# FilterBoard_Schematic.net
KiCad netlist of a schematic drawn in Altium Designer
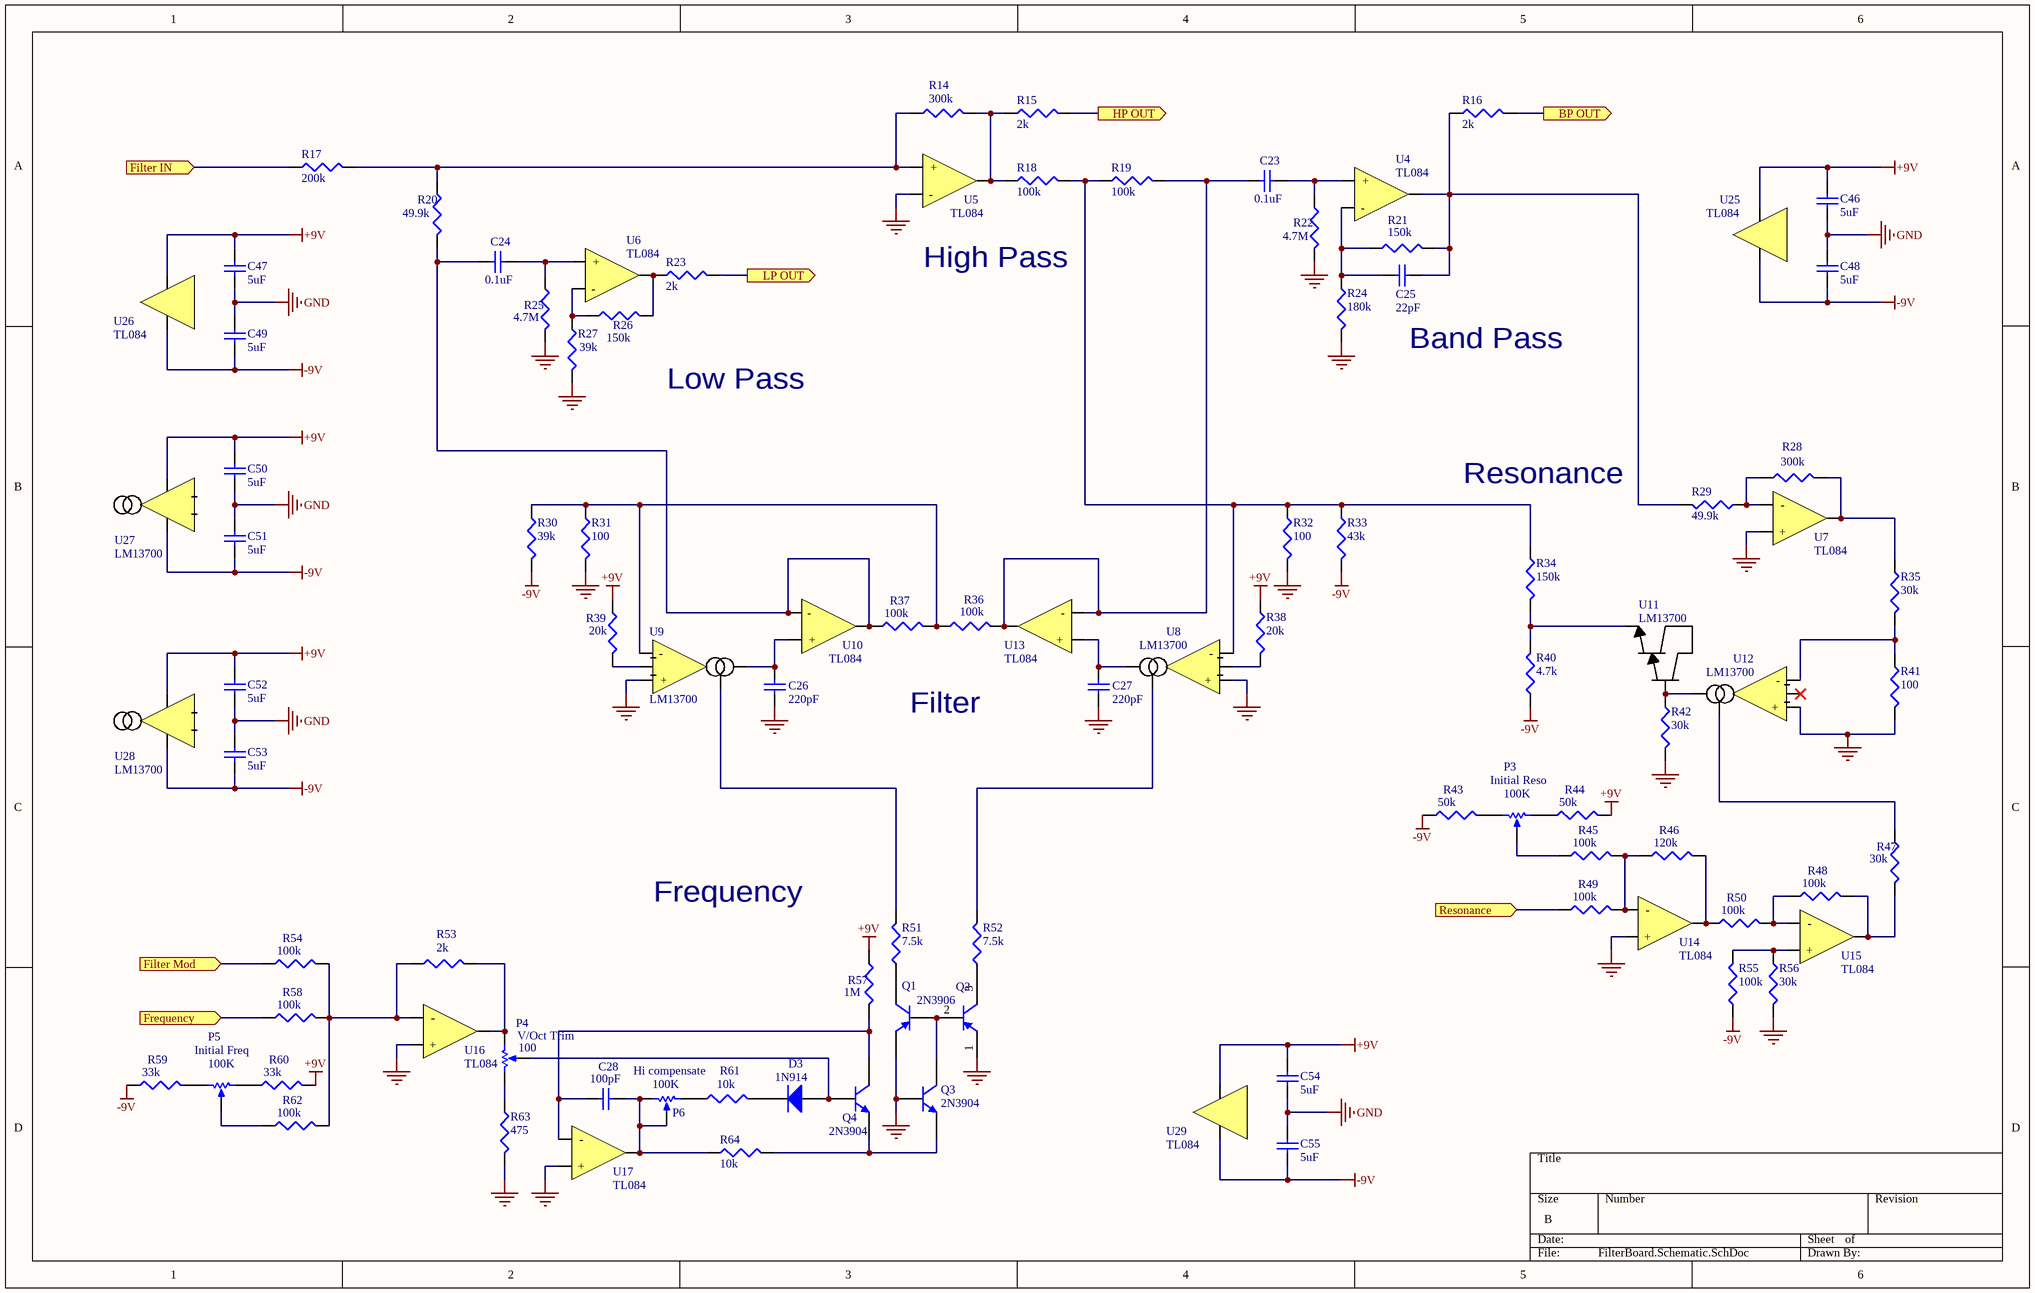
[diagram p0: FilterBoard.Schematic.SchDoc]

(export (version "E")
  (design (tool "Eeschema 10.0.6"))
  (components
    (comp (ref "C23")
      (value "0.1uF")
      (footprint "CAPC1608N")
      (description "Capacitor (Semiconductor SIM Model)")
      (fields (field (name "PUBLISHER") "Altium Limited"))
      (libsource (lib "Miscellaneous Devices") (part "Cap Semi"))
    )
    (comp (ref "C24")
      (value "0.1uF")
      (footprint "CAPC1608N")
      (description "Capacitor (Semiconductor SIM Model)")
      (fields (field (name "PUBLISHER") "Altium Limited"))
      (libsource (lib "Miscellaneous Devices") (part "Cap Semi"))
    )
    (comp (ref "C25")
      (value "22pF")
      (footprint "CAPC1608N")
      (description "Capacitor (Semiconductor SIM Model)")
      (fields (field (name "PUBLISHER") "Altium Limited"))
      (libsource (lib "Miscellaneous Devices") (part "Cap Semi"))
    )
    (comp (ref "C26")
      (value "220pF")
      (footprint "CAPC1608N")
      (description "Capacitor (Semiconductor SIM Model)")
      (fields (field (name "PUBLISHER") "Altium Limited"))
      (libsource (lib "Miscellaneous Devices") (part "Cap Semi"))
    )
    (comp (ref "C27")
      (value "220pF")
      (footprint "CAPC1608N")
      (description "Capacitor (Semiconductor SIM Model)")
      (fields (field (name "PUBLISHER") "Altium Limited"))
      (libsource (lib "Miscellaneous Devices") (part "Cap Semi"))
    )
    (comp (ref "C28")
      (value "100pF")
      (footprint "CAPC1608N")
      (description "Capacitor (Semiconductor SIM Model)")
      (fields (field (name "PUBLISHER") "Altium Limited"))
      (libsource (lib "Miscellaneous Devices") (part "Cap Semi"))
    )
    (comp (ref "C46")
      (value "5uF")
      (footprint "CAPC1608N")
      (description "Capacitor (Semiconductor SIM Model)")
      (fields (field (name "PUBLISHER") "Altium Limited"))
      (libsource (lib "Miscellaneous Devices") (part "Cap Semi"))
    )
    (comp (ref "C47")
      (value "5uF")
      (footprint "CAPC1608N")
      (description "Capacitor (Semiconductor SIM Model)")
      (fields (field (name "PUBLISHER") "Altium Limited"))
      (libsource (lib "Miscellaneous Devices") (part "Cap Semi"))
    )
    (comp (ref "C48")
      (value "5uF")
      (footprint "CAPC1608N")
      (description "Capacitor (Semiconductor SIM Model)")
      (fields (field (name "PUBLISHER") "Altium Limited"))
      (libsource (lib "Miscellaneous Devices") (part "Cap Semi"))
    )
    (comp (ref "C49")
      (value "5uF")
      (footprint "CAPC1608N")
      (description "Capacitor (Semiconductor SIM Model)")
      (fields (field (name "PUBLISHER") "Altium Limited"))
      (libsource (lib "Miscellaneous Devices") (part "Cap Semi"))
    )
    (comp (ref "C50")
      (value "5uF")
      (footprint "CAPC1608N")
      (description "Capacitor (Semiconductor SIM Model)")
      (fields (field (name "PUBLISHER") "Altium Limited"))
      (libsource (lib "Miscellaneous Devices") (part "Cap Semi"))
    )
    (comp (ref "C51")
      (value "5uF")
      (footprint "CAPC1608N")
      (description "Capacitor (Semiconductor SIM Model)")
      (fields (field (name "PUBLISHER") "Altium Limited"))
      (libsource (lib "Miscellaneous Devices") (part "Cap Semi"))
    )
    (comp (ref "C52")
      (value "5uF")
      (footprint "CAPC1608N")
      (description "Capacitor (Semiconductor SIM Model)")
      (fields (field (name "PUBLISHER") "Altium Limited"))
      (libsource (lib "Miscellaneous Devices") (part "Cap Semi"))
    )
    (comp (ref "C53")
      (value "5uF")
      (footprint "CAPC1608N")
      (description "Capacitor (Semiconductor SIM Model)")
      (fields (field (name "PUBLISHER") "Altium Limited"))
      (libsource (lib "Miscellaneous Devices") (part "Cap Semi"))
    )
    (comp (ref "C54")
      (value "5uF")
      (footprint "CAPC1608N")
      (description "Capacitor (Semiconductor SIM Model)")
      (fields (field (name "PUBLISHER") "Altium Limited"))
      (libsource (lib "Miscellaneous Devices") (part "Cap Semi"))
    )
    (comp (ref "C55")
      (value "5uF")
      (footprint "CAPC1608N")
      (description "Capacitor (Semiconductor SIM Model)")
      (fields (field (name "PUBLISHER") "Altium Limited"))
      (libsource (lib "Miscellaneous Devices") (part "Cap Semi"))
    )
    (comp (ref "D3")
      (value "1N914")
      (footprint "1N914")
      (description "1 Amp General Purpose Rectifier")
      (fields (field (name "PUBLISHER") "Altium Limited"))
      (libsource (lib "Miscellaneous Devices") (part "Diode 1N4001"))
    )
    (comp (ref "P3")
      (value "Initial Reso")
      (footprint "BOURNS Trim pot")
      (description "Potentiometer")
      (fields (field (name "ALTIUM_VALUE") "100K") (field (name "PUBLISHER") "Altium Limited"))
      (libsource (lib "Miscellaneous Devices") (part "RPot"))
    )
    (comp (ref "P4")
      (value "V/Oct Trim")
      (footprint "BOURNS Trim pot")
      (description "Potentiometer")
      (fields (field (name "ALTIUM_VALUE") "100") (field (name "PUBLISHER") "Altium Limited"))
      (libsource (lib "Miscellaneous Devices") (part "RPot"))
    )
    (comp (ref "P5")
      (value "Initial Freq")
      (footprint "BOURNS Trim pot")
      (description "Potentiometer")
      (fields (field (name "ALTIUM_VALUE") "100K") (field (name "PUBLISHER") "Altium Limited"))
      (libsource (lib "Miscellaneous Devices") (part "RPot"))
    )
    (comp (ref "P6")
      (value "Hi compensate")
      (footprint "BOURNS Trim pot")
      (description "Potentiometer")
      (fields (field (name "ALTIUM_VALUE") "100K") (field (name "PUBLISHER") "Altium Limited"))
      (libsource (lib "Miscellaneous Devices") (part "RPot"))
    )
    (comp (ref "Q1")
      (value "2N3906")
      (footprint "2N3906")
      (description "PNP General Purpose Amplifier")
      (fields (field (name "PUBLISHER") "Altium Limited"))
      (libsource (lib "") (part "2N3906_1"))
    )
    (comp (ref "Q2")
      (value "2N3906")
      (footprint "2N3906")
      (description "PNP General Purpose Amplifier")
      (fields (field (name "PUBLISHER") "Altium Limited"))
      (libsource (lib "Miscellaneous Devices") (part "2N3906"))
    )
    (comp (ref "Q3")
      (value "2N3904")
      (footprint "2N3906")
      (description "NPN General Purpose Amplifier")
      (fields (field (name "PUBLISHER") "Altium Limited"))
      (libsource (lib "Miscellaneous Devices") (part "2N3904"))
    )
    (comp (ref "Q4")
      (value "2N3904")
      (footprint "2N3906")
      (description "NPN General Purpose Amplifier")
      (fields (field (name "PUBLISHER") "Altium Limited"))
      (libsource (lib "Miscellaneous Devices") (part "2N3904"))
    )
    (comp (ref "R14")
      (value "300k")
      (footprint "CAPC1608N")
      (description "Resistor")
      (fields (field (name "PUBLISHER") "Altium Limited"))
      (libsource (lib "Miscellaneous Devices") (part "Res3"))
    )
    (comp (ref "R15")
      (value "2k")
      (footprint "CAPC1608N")
      (description "Resistor")
      (fields (field (name "PUBLISHER") "Altium Limited"))
      (libsource (lib "Miscellaneous Devices") (part "Res3"))
    )
    (comp (ref "R16")
      (value "2k")
      (footprint "CAPC1608N")
      (description "Resistor")
      (fields (field (name "PUBLISHER") "Altium Limited"))
      (libsource (lib "Miscellaneous Devices") (part "Res3"))
    )
    (comp (ref "R17")
      (value "200k")
      (footprint "CAPC1608N")
      (description "Resistor")
      (fields (field (name "PUBLISHER") "Altium Limited"))
      (libsource (lib "Miscellaneous Devices") (part "Res3"))
    )
    (comp (ref "R18")
      (value "100k")
      (footprint "CAPC1608N")
      (description "Resistor")
      (fields (field (name "PUBLISHER") "Altium Limited"))
      (libsource (lib "Miscellaneous Devices") (part "Res3"))
    )
    (comp (ref "R19")
      (value "100k")
      (footprint "CAPC1608N")
      (description "Resistor")
      (fields (field (name "PUBLISHER") "Altium Limited"))
      (libsource (lib "Miscellaneous Devices") (part "Res3"))
    )
    (comp (ref "R20")
      (value "49.9k")
      (footprint "CAPC1608N")
      (description "Resistor")
      (fields (field (name "PUBLISHER") "Altium Limited"))
      (libsource (lib "Miscellaneous Devices") (part "Res3"))
    )
    (comp (ref "R21")
      (value "150k")
      (footprint "CAPC1608N")
      (description "Resistor")
      (fields (field (name "PUBLISHER") "Altium Limited"))
      (libsource (lib "Miscellaneous Devices") (part "Res3"))
    )
    (comp (ref "R22")
      (value "4.7M")
      (footprint "CAPC1608N")
      (description "Resistor")
      (fields (field (name "PUBLISHER") "Altium Limited"))
      (libsource (lib "Miscellaneous Devices") (part "Res3"))
    )
    (comp (ref "R23")
      (value "2k")
      (footprint "CAPC1608N")
      (description "Resistor")
      (fields (field (name "PUBLISHER") "Altium Limited"))
      (libsource (lib "Miscellaneous Devices") (part "Res3"))
    )
    (comp (ref "R24")
      (value "180k")
      (footprint "CAPC1608N")
      (description "Resistor")
      (fields (field (name "PUBLISHER") "Altium Limited"))
      (libsource (lib "Miscellaneous Devices") (part "Res3"))
    )
    (comp (ref "R25")
      (value "4.7M")
      (footprint "CAPC1608N")
      (description "Resistor")
      (fields (field (name "PUBLISHER") "Altium Limited"))
      (libsource (lib "Miscellaneous Devices") (part "Res3"))
    )
    (comp (ref "R26")
      (value "150k")
      (footprint "CAPC1608N")
      (description "Resistor")
      (fields (field (name "PUBLISHER") "Altium Limited"))
      (libsource (lib "Miscellaneous Devices") (part "Res3"))
    )
    (comp (ref "R27")
      (value "39k")
      (footprint "CAPC1608N")
      (description "Resistor")
      (fields (field (name "PUBLISHER") "Altium Limited"))
      (libsource (lib "Miscellaneous Devices") (part "Res3"))
    )
    (comp (ref "R28")
      (value "300k")
      (footprint "CAPC1608N")
      (description "Resistor")
      (fields (field (name "PUBLISHER") "Altium Limited"))
      (libsource (lib "Miscellaneous Devices") (part "Res3"))
    )
    (comp (ref "R29")
      (value "49.9k")
      (footprint "CAPC1608N")
      (description "Resistor")
      (fields (field (name "PUBLISHER") "Altium Limited"))
      (libsource (lib "Miscellaneous Devices") (part "Res3"))
    )
    (comp (ref "R30")
      (value "39k")
      (footprint "CAPC1608N")
      (description "Resistor")
      (fields (field (name "PUBLISHER") "Altium Limited"))
      (libsource (lib "Miscellaneous Devices") (part "Res3"))
    )
    (comp (ref "R31")
      (value "100")
      (footprint "CAPC1608N")
      (description "Resistor")
      (fields (field (name "PUBLISHER") "Altium Limited"))
      (libsource (lib "Miscellaneous Devices") (part "Res3"))
    )
    (comp (ref "R32")
      (value "100")
      (footprint "CAPC1608N")
      (description "Resistor")
      (fields (field (name "PUBLISHER") "Altium Limited"))
      (libsource (lib "Miscellaneous Devices") (part "Res3"))
    )
    (comp (ref "R33")
      (value "43k")
      (footprint "CAPC1608N")
      (description "Resistor")
      (fields (field (name "PUBLISHER") "Altium Limited"))
      (libsource (lib "Miscellaneous Devices") (part "Res3"))
    )
    (comp (ref "R34")
      (value "150k")
      (footprint "CAPC1608N")
      (description "Resistor")
      (fields (field (name "PUBLISHER") "Altium Limited"))
      (libsource (lib "Miscellaneous Devices") (part "Res3"))
    )
    (comp (ref "R35")
      (value "30k")
      (footprint "CAPC1608N")
      (description "Resistor")
      (fields (field (name "PUBLISHER") "Altium Limited"))
      (libsource (lib "Miscellaneous Devices") (part "Res3"))
    )
    (comp (ref "R36")
      (value "100k")
      (footprint "CAPC1608N")
      (description "Resistor")
      (fields (field (name "PUBLISHER") "Altium Limited"))
      (libsource (lib "Miscellaneous Devices") (part "Res3"))
    )
    (comp (ref "R37")
      (value "100k")
      (footprint "CAPC1608N")
      (description "Resistor")
      (fields (field (name "PUBLISHER") "Altium Limited"))
      (libsource (lib "Miscellaneous Devices") (part "Res3"))
    )
    (comp (ref "R38")
      (value "20k")
      (footprint "CAPC1608N")
      (description "Resistor")
      (fields (field (name "PUBLISHER") "Altium Limited"))
      (libsource (lib "Miscellaneous Devices") (part "Res3"))
    )
    (comp (ref "R39")
      (value "20k")
      (footprint "CAPC1608N")
      (description "Resistor")
      (fields (field (name "PUBLISHER") "Altium Limited"))
      (libsource (lib "Miscellaneous Devices") (part "Res3"))
    )
    (comp (ref "R40")
      (value "4.7k")
      (footprint "CAPC1608N")
      (description "Resistor")
      (fields (field (name "PUBLISHER") "Altium Limited"))
      (libsource (lib "Miscellaneous Devices") (part "Res3"))
    )
    (comp (ref "R41")
      (value "100")
      (footprint "CAPC1608N")
      (description "Resistor")
      (fields (field (name "PUBLISHER") "Altium Limited"))
      (libsource (lib "Miscellaneous Devices") (part "Res3"))
    )
    (comp (ref "R42")
      (value "30k")
      (footprint "CAPC1608N")
      (description "Resistor")
      (fields (field (name "PUBLISHER") "Altium Limited"))
      (libsource (lib "Miscellaneous Devices") (part "Res3"))
    )
    (comp (ref "R43")
      (value "50k")
      (footprint "CAPC1608N")
      (description "Resistor")
      (fields (field (name "PUBLISHER") "Altium Limited"))
      (libsource (lib "Miscellaneous Devices") (part "Res3"))
    )
    (comp (ref "R44")
      (value "50k")
      (footprint "CAPC1608N")
      (description "Resistor")
      (fields (field (name "PUBLISHER") "Altium Limited"))
      (libsource (lib "Miscellaneous Devices") (part "Res3"))
    )
    (comp (ref "R45")
      (value "100k")
      (footprint "CAPC1608N")
      (description "Resistor")
      (fields (field (name "PUBLISHER") "Altium Limited"))
      (libsource (lib "Miscellaneous Devices") (part "Res3"))
    )
    (comp (ref "R46")
      (value "120k")
      (footprint "CAPC1608N")
      (description "Resistor")
      (fields (field (name "PUBLISHER") "Altium Limited"))
      (libsource (lib "Miscellaneous Devices") (part "Res3"))
    )
    (comp (ref "R47")
      (value "30k")
      (footprint "CAPC1608N")
      (description "Resistor")
      (fields (field (name "PUBLISHER") "Altium Limited"))
      (libsource (lib "Miscellaneous Devices") (part "Res3"))
    )
    (comp (ref "R48")
      (value "100k")
      (footprint "CAPC1608N")
      (description "Resistor")
      (fields (field (name "PUBLISHER") "Altium Limited"))
      (libsource (lib "Miscellaneous Devices") (part "Res3"))
    )
    (comp (ref "R49")
      (value "100k")
      (footprint "CAPC1608N")
      (description "Resistor")
      (fields (field (name "PUBLISHER") "Altium Limited"))
      (libsource (lib "Miscellaneous Devices") (part "Res3"))
    )
    (comp (ref "R50")
      (value "100k")
      (footprint "CAPC1608N")
      (description "Resistor")
      (fields (field (name "PUBLISHER") "Altium Limited"))
      (libsource (lib "Miscellaneous Devices") (part "Res3"))
    )
    (comp (ref "R51")
      (value "7.5k")
      (footprint "CAPC1608N")
      (description "Resistor")
      (fields (field (name "PUBLISHER") "Altium Limited"))
      (libsource (lib "Miscellaneous Devices") (part "Res3"))
    )
    (comp (ref "R52")
      (value "7.5k")
      (footprint "CAPC1608N")
      (description "Resistor")
      (fields (field (name "PUBLISHER") "Altium Limited"))
      (libsource (lib "Miscellaneous Devices") (part "Res3"))
    )
    (comp (ref "R53")
      (value "2k")
      (footprint "CAPC1608N")
      (description "Resistor")
      (fields (field (name "PUBLISHER") "Altium Limited"))
      (libsource (lib "Miscellaneous Devices") (part "Res3"))
    )
    (comp (ref "R54")
      (value "100k")
      (footprint "CAPC1608N")
      (description "Resistor")
      (fields (field (name "PUBLISHER") "Altium Limited"))
      (libsource (lib "Miscellaneous Devices") (part "Res3"))
    )
    (comp (ref "R55")
      (value "100k")
      (footprint "CAPC1608N")
      (description "Resistor")
      (fields (field (name "PUBLISHER") "Altium Limited"))
      (libsource (lib "Miscellaneous Devices") (part "Res3"))
    )
    (comp (ref "R56")
      (value "30k")
      (footprint "CAPC1608N")
      (description "Resistor")
      (fields (field (name "PUBLISHER") "Altium Limited"))
      (libsource (lib "Miscellaneous Devices") (part "Res3"))
    )
    (comp (ref "R57")
      (value "1M")
      (footprint "CAPC1608N")
      (description "Resistor")
      (fields (field (name "PUBLISHER") "Altium Limited"))
      (libsource (lib "Miscellaneous Devices") (part "Res3"))
    )
    (comp (ref "R58")
      (value "100k")
      (footprint "CAPC1608N")
      (description "Resistor")
      (fields (field (name "PUBLISHER") "Altium Limited"))
      (libsource (lib "Miscellaneous Devices") (part "Res3"))
    )
    (comp (ref "R59")
      (value "33k")
      (footprint "CAPC1608N")
      (description "Resistor")
      (fields (field (name "PUBLISHER") "Altium Limited"))
      (libsource (lib "Miscellaneous Devices") (part "Res3"))
    )
    (comp (ref "R60")
      (value "33k")
      (footprint "CAPC1608N")
      (description "Resistor")
      (fields (field (name "PUBLISHER") "Altium Limited"))
      (libsource (lib "Miscellaneous Devices") (part "Res3"))
    )
    (comp (ref "R61")
      (value "10k")
      (footprint "CAPC1608N")
      (description "Resistor")
      (fields (field (name "PUBLISHER") "Altium Limited"))
      (libsource (lib "Miscellaneous Devices") (part "Res3"))
    )
    (comp (ref "R62")
      (value "100k")
      (footprint "CAPC1608N")
      (description "Resistor")
      (fields (field (name "PUBLISHER") "Altium Limited"))
      (libsource (lib "Miscellaneous Devices") (part "Res3"))
    )
    (comp (ref "R63")
      (value "475")
      (footprint "CAPC1608N")
      (description "Resistor")
      (fields (field (name "PUBLISHER") "Altium Limited"))
      (libsource (lib "Miscellaneous Devices") (part "Res3"))
    )
    (comp (ref "R64")
      (value "10k")
      (footprint "CAPC1608N")
      (description "Resistor")
      (fields (field (name "PUBLISHER") "Altium Limited"))
      (libsource (lib "Miscellaneous Devices") (part "Res3"))
    )
    (comp (ref "U4")
      (value "TL084")
      (footprint "TL084_3PADS")
      (libsource (lib "SynthyTwo.Components") (part "TL084"))
    )
    (comp (ref "U5")
      (value "TL084")
      (footprint "TL084_3PADS")
      (libsource (lib "SynthyTwo.Components") (part "TL084"))
    )
    (comp (ref "U6")
      (value "TL084")
      (footprint "TL084_3PADS")
      (libsource (lib "SynthyTwo.Components") (part "TL084"))
    )
    (comp (ref "U7") (value "TL084") (footprint "TL084_3PADS") (libsource (lib "") (part "TL084_1")))
    (comp (ref "U8")
      (value "LM13700")
      (footprint "LM13700_5PADS")
      (libsource (lib "SynthyTwo.Components") (part "LM13700_2"))
    )
    (comp (ref "U9")
      (value "LM13700")
      (footprint "LM13700_5PADS")
      (libsource (lib "SynthyTwo.Components") (part "LM13700_2"))
    )
    (comp (ref "U10")
      (value "TL084")
      (footprint "TL084_3PADS")
      (libsource (lib "SynthyTwo.Components") (part "TL084"))
    )
    (comp (ref "U11")
      (value "LM13700")
      (footprint "LM13700_2PADS")
      (libsource (lib "SynthyTwo.Components") (part "LM13700_1"))
    )
    (comp (ref "U12")
      (value "LM13700")
      (footprint "LM13700_5PADS")
      (libsource (lib "SynthyTwo.Components") (part "LM13700_2"))
    )
    (comp (ref "U13")
      (value "TL084")
      (footprint "TL084_3PADS")
      (libsource (lib "SynthyTwo.Components") (part "TL084"))
    )
    (comp (ref "U14") (value "TL084") (footprint "TL084_3PADS") (libsource (lib "") (part "TL084_1")))
    (comp (ref "U15") (value "TL084") (footprint "TL084_3PADS") (libsource (lib "") (part "TL084_1")))
    (comp (ref "U16") (value "TL084") (footprint "TL084_3PADS") (libsource (lib "") (part "TL084_1")))
    (comp (ref "U17") (value "TL084") (footprint "TL084_3PADS") (libsource (lib "") (part "TL084_1")))
    (comp (ref "U25")
      (value "TL084")
      (footprint "TL084_ALIM")
      (libsource (lib "SynthyTwo.Components") (part "TL_CLEAN"))
    )
    (comp (ref "U26")
      (value "TL084")
      (footprint "TL084_ALIM")
      (libsource (lib "SynthyTwo.Components") (part "TL_CLEAN"))
    )
    (comp (ref "U27")
      (value "LM13700")
      (footprint "LM13700_ALIM")
      (libsource (lib "SynthyTwo.Components") (part "LM13700"))
    )
    (comp (ref "U28")
      (value "LM13700")
      (footprint "LM13700_ALIM")
      (libsource (lib "SynthyTwo.Components") (part "LM13700"))
    )
    (comp (ref "U29")
      (value "TL084")
      (footprint "TL084_ALIM")
      (libsource (lib "SynthyTwo.Components") (part "TL_CLEAN"))
    )
  )
  (nets
    (net (code "1") (name "+9V") (class "Default")
      (node (ref "C46") (pin "1") (pinfunction "1_1") (pintype "passive"))
      (node (ref "C47") (pin "1") (pinfunction "1_1") (pintype "passive"))
      (node (ref "C50") (pin "1") (pinfunction "1_1") (pintype "passive"))
      (node (ref "C52") (pin "1") (pinfunction "1_1") (pintype "passive"))
      (node (ref "C54") (pin "1") (pinfunction "1_1") (pintype "passive"))
      (node (ref "R38") (pin "1") (pinfunction "1_1") (pintype "passive"))
      (node (ref "R39") (pin "1") (pinfunction "1_1") (pintype "passive"))
      (node (ref "R44") (pin "2") (pinfunction "2_2") (pintype "passive"))
      (node (ref "R57") (pin "1") (pinfunction "1_1") (pintype "passive"))
      (node (ref "R60") (pin "2") (pinfunction "2_2") (pintype "passive"))
      (node (ref "U25") (pin "2") (pinfunction "VCC-_2") (pintype "passive"))
      (node (ref "U26") (pin "2") (pinfunction "VCC-_2") (pintype "passive"))
      (node (ref "U27") (pin "1") (pinfunction "VCC+_1") (pintype "passive"))
      (node (ref "U28") (pin "1") (pinfunction "VCC+_1") (pintype "passive"))
      (node (ref "U29") (pin "2") (pinfunction "VCC-_2") (pintype "passive"))
    )
    (net (code "2") (name "-9V") (class "Default")
      (node (ref "C48") (pin "2") (pinfunction "2_2") (pintype "passive"))
      (node (ref "C49") (pin "2") (pinfunction "2_2") (pintype "passive"))
      (node (ref "C51") (pin "2") (pinfunction "2_2") (pintype "passive"))
      (node (ref "C53") (pin "2") (pinfunction "2_2") (pintype "passive"))
      (node (ref "C55") (pin "2") (pinfunction "2_2") (pintype "passive"))
      (node (ref "R30") (pin "2") (pinfunction "2_2") (pintype "passive"))
      (node (ref "R33") (pin "2") (pinfunction "2_2") (pintype "passive"))
      (node (ref "R40") (pin "1") (pinfunction "1_1") (pintype "passive"))
      (node (ref "R43") (pin "1") (pinfunction "1_1") (pintype "passive"))
      (node (ref "R55") (pin "1") (pinfunction "1_1") (pintype "passive"))
      (node (ref "R59") (pin "1") (pinfunction "1_1") (pintype "passive"))
      (node (ref "U25") (pin "1") (pinfunction "VCC+_1") (pintype "passive"))
      (node (ref "U26") (pin "1") (pinfunction "VCC+_1") (pintype "passive"))
      (node (ref "U29") (pin "1") (pinfunction "VCC+_1") (pintype "passive"))
    )
    (net (code "3") (name "/BP OUT") (class "Default")
      (node (ref "R16") (pin "2") (pinfunction "2_2") (pintype "passive"))
    )
    (net (code "4") (name "/Filter IN") (class "Default")
      (node (ref "R17") (pin "1") (pinfunction "1_1") (pintype "passive"))
    )
    (net (code "5") (name "/Filter Mod") (class "Default")
      (node (ref "R54") (pin "1") (pinfunction "1_1") (pintype "passive"))
    )
    (net (code "6") (name "/Frequency") (class "Default")
      (node (ref "R58") (pin "1") (pinfunction "1_1") (pintype "passive"))
    )
    (net (code "7") (name "/HP OUT") (class "Default")
      (node (ref "R15") (pin "2") (pinfunction "2_2") (pintype "passive"))
    )
    (net (code "8") (name "/LP OUT") (class "Default")
      (node (ref "R23") (pin "2") (pinfunction "2_2") (pintype "passive"))
    )
    (net (code "9") (name "/Resonance") (class "Default")
      (node (ref "R49") (pin "1") (pinfunction "1_1") (pintype "passive"))
    )
    (net (code "10") (name "GND") (class "Default")
      (node (ref "C26") (pin "1") (pinfunction "1_1") (pintype "passive"))
      (node (ref "C27") (pin "1") (pinfunction "1_1") (pintype "passive"))
      (node (ref "C46") (pin "2") (pinfunction "2_2") (pintype "passive"))
      (node (ref "C47") (pin "2") (pinfunction "2_2") (pintype "passive"))
      (node (ref "C48") (pin "1") (pinfunction "1_1") (pintype "passive"))
      (node (ref "C49") (pin "1") (pinfunction "1_1") (pintype "passive"))
      (node (ref "C50") (pin "2") (pinfunction "2_2") (pintype "passive"))
      (node (ref "C51") (pin "1") (pinfunction "1_1") (pintype "passive"))
      (node (ref "C52") (pin "2") (pinfunction "2_2") (pintype "passive"))
      (node (ref "C53") (pin "1") (pinfunction "1_1") (pintype "passive"))
      (node (ref "C54") (pin "2") (pinfunction "2_2") (pintype "passive"))
      (node (ref "C55") (pin "1") (pinfunction "1_1") (pintype "passive"))
      (node (ref "Q1") (pin "1") (pinfunction "E_1") (pintype "passive"))
      (node (ref "Q2") (pin "1") (pinfunction "E_1") (pintype "passive"))
      (node (ref "Q3") (pin "2") (pinfunction "B_2") (pintype "passive"))
      (node (ref "R22") (pin "2") (pinfunction "2_2") (pintype "passive"))
      (node (ref "R24") (pin "2") (pinfunction "2_2") (pintype "passive"))
      (node (ref "R25") (pin "2") (pinfunction "2_2") (pintype "passive"))
      (node (ref "R27") (pin "2") (pinfunction "2_2") (pintype "passive"))
      (node (ref "R31") (pin "2") (pinfunction "2_2") (pintype "passive"))
      (node (ref "R32") (pin "2") (pinfunction "2_2") (pintype "passive"))
      (node (ref "R41") (pin "2") (pinfunction "2_2") (pintype "passive"))
      (node (ref "R42") (pin "2") (pinfunction "2_2") (pintype "passive"))
      (node (ref "R56") (pin "2") (pinfunction "2_2") (pintype "passive"))
      (node (ref "R63") (pin "2") (pinfunction "2_2") (pintype "passive"))
      (node (ref "U12") (pin "3") (pinfunction "+_3") (pintype "passive"))
      (node (ref "U14") (pin "3") (pinfunction "+_3") (pintype "passive"))
      (node (ref "U16") (pin "3") (pinfunction "+_3") (pintype "passive"))
      (node (ref "U17") (pin "3") (pinfunction "+_3") (pintype "passive"))
      (node (ref "U5") (pin "2") (pinfunction "-_2") (pintype "passive"))
      (node (ref "U7") (pin "3") (pinfunction "+_3") (pintype "passive"))
      (node (ref "U8") (pin "3") (pinfunction "+_3") (pintype "passive"))
      (node (ref "U9") (pin "3") (pinfunction "+_3") (pintype "passive"))
    )
    (net (code "11") (name "Net-(D3-A)") (class "Default")
      (node (ref "D3") (pin "1") (pinfunction "A_1") (pintype "passive"))
      (node (ref "P4") (pin "3") (pinfunction "TAP_3") (pintype "passive"))
      (node (ref "Q4") (pin "2") (pinfunction "B_2") (pintype "passive"))
    )
    (net (code "12") (name "Net-(D3-K)") (class "Default")
      (node (ref "D3") (pin "2") (pinfunction "K_2") (pintype "passive"))
      (node (ref "R61") (pin "2") (pinfunction "2_2") (pintype "passive"))
    )
    (net (code "13") (name "Net-(P3-BOT)") (class "Default")
      (node (ref "P3") (pin "2") (pinfunction "BOT_2") (pintype "passive"))
      (node (ref "R43") (pin "2") (pinfunction "2_2") (pintype "passive"))
    )
    (net (code "14") (name "Net-(P3-TAP)") (class "Default")
      (node (ref "P3") (pin "3") (pinfunction "TAP_3") (pintype "passive"))
      (node (ref "R45") (pin "1") (pinfunction "1_1") (pintype "passive"))
    )
    (net (code "15") (name "Net-(P3-TOP)") (class "Default")
      (node (ref "P3") (pin "1") (pinfunction "TOP_1") (pintype "passive"))
      (node (ref "R44") (pin "1") (pinfunction "1_1") (pintype "passive"))
    )
    (net (code "16") (name "Net-(P4-BOT)") (class "Default")
      (node (ref "P4") (pin "2") (pinfunction "BOT_2") (pintype "passive"))
      (node (ref "R63") (pin "1") (pinfunction "1_1") (pintype "passive"))
    )
    (net (code "17") (name "Net-(P4-TOP)") (class "Default")
      (node (ref "P4") (pin "1") (pinfunction "TOP_1") (pintype "passive"))
      (node (ref "R53") (pin "2") (pinfunction "2_2") (pintype "passive"))
      (node (ref "U16") (pin "1") (pinfunction "OUT_1") (pintype "passive"))
    )
    (net (code "18") (name "Net-(P5-BOT)") (class "Default")
      (node (ref "P5") (pin "2") (pinfunction "BOT_2") (pintype "passive"))
      (node (ref "R59") (pin "2") (pinfunction "2_2") (pintype "passive"))
    )
    (net (code "19") (name "Net-(P5-TAP)") (class "Default")
      (node (ref "P5") (pin "3") (pinfunction "TAP_3") (pintype "passive"))
      (node (ref "R62") (pin "1") (pinfunction "1_1") (pintype "passive"))
    )
    (net (code "20") (name "Net-(P5-TOP)") (class "Default")
      (node (ref "P5") (pin "1") (pinfunction "TOP_1") (pintype "passive"))
      (node (ref "R60") (pin "1") (pinfunction "1_1") (pintype "passive"))
    )
    (net (code "21") (name "Net-(P6-BOT)") (class "Default")
      (node (ref "C28") (pin "2") (pinfunction "2_2") (pintype "passive"))
      (node (ref "P6") (pin "2") (pinfunction "BOT_2") (pintype "passive"))
      (node (ref "P6") (pin "3") (pinfunction "TAP_3") (pintype "passive"))
      (node (ref "R64") (pin "1") (pinfunction "1_1") (pintype "passive"))
      (node (ref "U17") (pin "1") (pinfunction "OUT_1") (pintype "passive"))
    )
    (net (code "22") (name "Net-(P6-TOP)") (class "Default")
      (node (ref "P6") (pin "1") (pinfunction "TOP_1") (pintype "passive"))
      (node (ref "R61") (pin "1") (pinfunction "1_1") (pintype "passive"))
    )
    (net (code "23") (name "Net-(Q1-B)") (class "Default")
      (node (ref "Q1") (pin "2") (pinfunction "B_2") (pintype "passive"))
      (node (ref "Q2") (pin "2") (pinfunction "B_2") (pintype "passive"))
      (node (ref "Q3") (pin "3") (pinfunction "C_3") (pintype "passive"))
    )
    (net (code "24") (name "Net-(Q1-C)") (class "Default")
      (node (ref "Q1") (pin "3") (pinfunction "C_3") (pintype "passive"))
      (node (ref "R51") (pin "1") (pinfunction "1_1") (pintype "passive"))
    )
    (net (code "25") (name "Net-(Q2-C)") (class "Default")
      (node (ref "Q2") (pin "3") (pinfunction "C_3") (pintype "passive"))
      (node (ref "R52") (pin "1") (pinfunction "1_1") (pintype "passive"))
    )
    (net (code "26") (name "Net-(Q3-E)") (class "Default")
      (node (ref "Q3") (pin "1") (pinfunction "E_1") (pintype "passive"))
      (node (ref "Q4") (pin "1") (pinfunction "E_1") (pintype "passive"))
      (node (ref "R64") (pin "2") (pinfunction "2_2") (pintype "passive"))
    )
    (net (code "27") (name "Net-(Q4-C)") (class "Default")
      (node (ref "C28") (pin "1") (pinfunction "1_1") (pintype "passive"))
      (node (ref "Q4") (pin "3") (pinfunction "C_3") (pintype "passive"))
      (node (ref "R57") (pin "2") (pinfunction "2_2") (pintype "passive"))
      (node (ref "U17") (pin "2") (pinfunction "-_2") (pintype "passive"))
    )
    (net (code "28") (name "Net-(R38-Pad2)") (class "Default")
      (node (ref "R38") (pin "2") (pinfunction "2_2") (pintype "passive"))
      (node (ref "U8") (pin "2") (pinfunction "2_2") (pintype "passive"))
    )
    (net (code "29") (name "Net-(R39-Pad2)") (class "Default")
      (node (ref "R39") (pin "2") (pinfunction "2_2") (pintype "passive"))
      (node (ref "U9") (pin "2") (pinfunction "2_2") (pintype "passive"))
    )
    (net (code "30") (name "Net-(U4-+)") (class "Default")
      (node (ref "C23") (pin "2") (pinfunction "2_2") (pintype "passive"))
      (node (ref "R22") (pin "1") (pinfunction "1_1") (pintype "passive"))
      (node (ref "U4") (pin "3") (pinfunction "+_3") (pintype "passive"))
    )
    (net (code "31") (name "Net-(U4--)") (class "Default")
      (node (ref "C25") (pin "1") (pinfunction "1_1") (pintype "passive"))
      (node (ref "R21") (pin "1") (pinfunction "1_1") (pintype "passive"))
      (node (ref "R24") (pin "1") (pinfunction "1_1") (pintype "passive"))
      (node (ref "U4") (pin "2") (pinfunction "-_2") (pintype "passive"))
    )
    (net (code "32") (name "Net-(U4-OUT)") (class "Default")
      (node (ref "C25") (pin "2") (pinfunction "2_2") (pintype "passive"))
      (node (ref "R16") (pin "1") (pinfunction "1_1") (pintype "passive"))
      (node (ref "R21") (pin "2") (pinfunction "2_2") (pintype "passive"))
      (node (ref "R29") (pin "2") (pinfunction "2_2") (pintype "passive"))
      (node (ref "U4") (pin "1") (pinfunction "OUT_1") (pintype "passive"))
    )
    (net (code "33") (name "Net-(U5-+)") (class "Default")
      (node (ref "R14") (pin "1") (pinfunction "1_1") (pintype "passive"))
      (node (ref "R17") (pin "2") (pinfunction "2_2") (pintype "passive"))
      (node (ref "R20") (pin "1") (pinfunction "1_1") (pintype "passive"))
      (node (ref "U5") (pin "3") (pinfunction "+_3") (pintype "passive"))
    )
    (net (code "34") (name "Net-(U5-OUT)") (class "Default")
      (node (ref "R14") (pin "2") (pinfunction "2_2") (pintype "passive"))
      (node (ref "R15") (pin "1") (pinfunction "1_1") (pintype "passive"))
      (node (ref "R18") (pin "1") (pinfunction "1_1") (pintype "passive"))
      (node (ref "U5") (pin "1") (pinfunction "OUT_1") (pintype "passive"))
    )
    (net (code "35") (name "Net-(U6-+)") (class "Default")
      (node (ref "C24") (pin "2") (pinfunction "2_2") (pintype "passive"))
      (node (ref "R25") (pin "1") (pinfunction "1_1") (pintype "passive"))
      (node (ref "U6") (pin "3") (pinfunction "+_3") (pintype "passive"))
    )
    (net (code "36") (name "Net-(U6--)") (class "Default")
      (node (ref "R26") (pin "1") (pinfunction "1_1") (pintype "passive"))
      (node (ref "R27") (pin "1") (pinfunction "1_1") (pintype "passive"))
      (node (ref "U6") (pin "2") (pinfunction "-_2") (pintype "passive"))
    )
    (net (code "37") (name "Net-(U6-OUT)") (class "Default")
      (node (ref "R23") (pin "1") (pinfunction "1_1") (pintype "passive"))
      (node (ref "R26") (pin "2") (pinfunction "2_2") (pintype "passive"))
      (node (ref "U6") (pin "1") (pinfunction "OUT_1") (pintype "passive"))
    )
    (net (code "38") (name "Net-(U7--)") (class "Default")
      (node (ref "R28") (pin "1") (pinfunction "1_1") (pintype "passive"))
      (node (ref "R29") (pin "1") (pinfunction "1_1") (pintype "passive"))
      (node (ref "U7") (pin "2") (pinfunction "-_2") (pintype "passive"))
    )
    (net (code "39") (name "Net-(U7-OUT)") (class "Default")
      (node (ref "R28") (pin "2") (pinfunction "2_2") (pintype "passive"))
      (node (ref "R35") (pin "1") (pinfunction "1_1") (pintype "passive"))
      (node (ref "U7") (pin "1") (pinfunction "OUT_1") (pintype "passive"))
    )
    (net (code "40") (name "Net-(U8--)") (class "Default")
      (node (ref "R18") (pin "2") (pinfunction "2_2") (pintype "passive"))
      (node (ref "R19") (pin "1") (pinfunction "1_1") (pintype "passive"))
      (node (ref "R32") (pin "1") (pinfunction "1_1") (pintype "passive"))
      (node (ref "R33") (pin "1") (pinfunction "1_1") (pintype "passive"))
      (node (ref "R34") (pin "1") (pinfunction "1_1") (pintype "passive"))
      (node (ref "U8") (pin "4") (pinfunction "-_4") (pintype "passive"))
    )
    (net (code "41") (name "Net-(U8-BIAS)") (class "Default")
      (node (ref "R52") (pin "2") (pinfunction "2_2") (pintype "passive"))
      (node (ref "U8") (pin "1") (pinfunction "BIAS_1") (pintype "passive"))
    )
    (net (code "42") (name "Net-(U9--)") (class "Default")
      (node (ref "R30") (pin "1") (pinfunction "1_1") (pintype "passive"))
      (node (ref "R31") (pin "1") (pinfunction "1_1") (pintype "passive"))
      (node (ref "R36") (pin "1") (pinfunction "1_1") (pintype "passive"))
      (node (ref "R37") (pin "2") (pinfunction "2_2") (pintype "passive"))
      (node (ref "U9") (pin "4") (pinfunction "-_4") (pintype "passive"))
    )
    (net (code "43") (name "Net-(U9-BIAS)") (class "Default")
      (node (ref "R51") (pin "2") (pinfunction "2_2") (pintype "passive"))
      (node (ref "U9") (pin "1") (pinfunction "BIAS_1") (pintype "passive"))
    )
    (net (code "44") (name "Net-(U10-+)") (class "Default")
      (node (ref "C26") (pin "2") (pinfunction "2_2") (pintype "passive"))
      (node (ref "U10") (pin "3") (pinfunction "+_3") (pintype "passive"))
      (node (ref "U9") (pin "5") (pinfunction "OUT_5") (pintype "passive"))
    )
    (net (code "45") (name "Net-(U10--)") (class "Default")
      (node (ref "C24") (pin "1") (pinfunction "1_1") (pintype "passive"))
      (node (ref "R20") (pin "2") (pinfunction "2_2") (pintype "passive"))
      (node (ref "R37") (pin "1") (pinfunction "1_1") (pintype "passive"))
      (node (ref "U10") (pin "1") (pinfunction "OUT_1") (pintype "passive"))
      (node (ref "U10") (pin "2") (pinfunction "-_2") (pintype "passive"))
    )
    (net (code "46") (name "Net-(U11-BIN)") (class "Default")
      (node (ref "R42") (pin "1") (pinfunction "1_1") (pintype "passive"))
      (node (ref "U11") (pin "1") (pinfunction "BIN_1") (pintype "passive"))
      (node (ref "U12") (pin "5") (pinfunction "OUT_5") (pintype "passive"))
    )
    (net (code "47") (name "Net-(U11-V+)") (class "Default")
      (node (ref "R34") (pin "2") (pinfunction "2_2") (pintype "passive"))
      (node (ref "R40") (pin "2") (pinfunction "2_2") (pintype "passive"))
      (node (ref "U11") (pin "2") (pinfunction "V+_2") (pintype "passive"))
    )
    (net (code "48") (name "Net-(U12--)") (class "Default")
      (node (ref "R35") (pin "2") (pinfunction "2_2") (pintype "passive"))
      (node (ref "R41") (pin "1") (pinfunction "1_1") (pintype "passive"))
      (node (ref "U12") (pin "4") (pinfunction "-_4") (pintype "passive"))
    )
    (net (code "49") (name "Net-(U12-BIAS)") (class "Default")
      (node (ref "R47") (pin "1") (pinfunction "1_1") (pintype "passive"))
      (node (ref "U12") (pin "1") (pinfunction "BIAS_1") (pintype "passive"))
    )
    (net (code "50") (name "Net-(U13-+)") (class "Default")
      (node (ref "C27") (pin "2") (pinfunction "2_2") (pintype "passive"))
      (node (ref "U13") (pin "3") (pinfunction "+_3") (pintype "passive"))
      (node (ref "U8") (pin "5") (pinfunction "OUT_5") (pintype "passive"))
    )
    (net (code "51") (name "Net-(U13--)") (class "Default")
      (node (ref "C23") (pin "1") (pinfunction "1_1") (pintype "passive"))
      (node (ref "R19") (pin "2") (pinfunction "2_2") (pintype "passive"))
      (node (ref "R36") (pin "2") (pinfunction "2_2") (pintype "passive"))
      (node (ref "U13") (pin "1") (pinfunction "OUT_1") (pintype "passive"))
      (node (ref "U13") (pin "2") (pinfunction "-_2") (pintype "passive"))
    )
    (net (code "52") (name "Net-(U14--)") (class "Default")
      (node (ref "R45") (pin "2") (pinfunction "2_2") (pintype "passive"))
      (node (ref "R46") (pin "1") (pinfunction "1_1") (pintype "passive"))
      (node (ref "R49") (pin "2") (pinfunction "2_2") (pintype "passive"))
      (node (ref "U14") (pin "2") (pinfunction "-_2") (pintype "passive"))
    )
    (net (code "53") (name "Net-(U14-OUT)") (class "Default")
      (node (ref "R46") (pin "2") (pinfunction "2_2") (pintype "passive"))
      (node (ref "R50") (pin "1") (pinfunction "1_1") (pintype "passive"))
      (node (ref "U14") (pin "1") (pinfunction "OUT_1") (pintype "passive"))
    )
    (net (code "54") (name "Net-(U15-+)") (class "Default")
      (node (ref "R55") (pin "2") (pinfunction "2_2") (pintype "passive"))
      (node (ref "R56") (pin "1") (pinfunction "1_1") (pintype "passive"))
      (node (ref "U15") (pin "3") (pinfunction "+_3") (pintype "passive"))
    )
    (net (code "55") (name "Net-(U15--)") (class "Default")
      (node (ref "R48") (pin "1") (pinfunction "1_1") (pintype "passive"))
      (node (ref "R50") (pin "2") (pinfunction "2_2") (pintype "passive"))
      (node (ref "U15") (pin "2") (pinfunction "-_2") (pintype "passive"))
    )
    (net (code "56") (name "Net-(U15-OUT)") (class "Default")
      (node (ref "R47") (pin "2") (pinfunction "2_2") (pintype "passive"))
      (node (ref "R48") (pin "2") (pinfunction "2_2") (pintype "passive"))
      (node (ref "U15") (pin "1") (pinfunction "OUT_1") (pintype "passive"))
    )
    (net (code "57") (name "Net-(U16--)") (class "Default")
      (node (ref "R53") (pin "1") (pinfunction "1_1") (pintype "passive"))
      (node (ref "R54") (pin "2") (pinfunction "2_2") (pintype "passive"))
      (node (ref "R58") (pin "2") (pinfunction "2_2") (pintype "passive"))
      (node (ref "R62") (pin "2") (pinfunction "2_2") (pintype "passive"))
      (node (ref "U16") (pin "2") (pinfunction "-_2") (pintype "passive"))
    )
    (net (code "58") (name "unconnected-(U12-Pad2)") (class "Default")
      (node (ref "U12") (pin "2") (pinfunction "2_2") (pintype "passive+no_connect"))
    )
    (net (code "59") (name "unconnected-(U27-VCC--Pad2)") (class "Default")
      (node (ref "U27") (pin "2") (pinfunction "VCC-_2") (pintype "passive"))
    )
    (net (code "60") (name "unconnected-(U28-VCC--Pad2)") (class "Default")
      (node (ref "U28") (pin "2") (pinfunction "VCC-_2") (pintype "passive"))
    )
  )
)
